# mainboard_motor_v1_6.net
KiCad netlist of a schematic drawn in Altium Designer
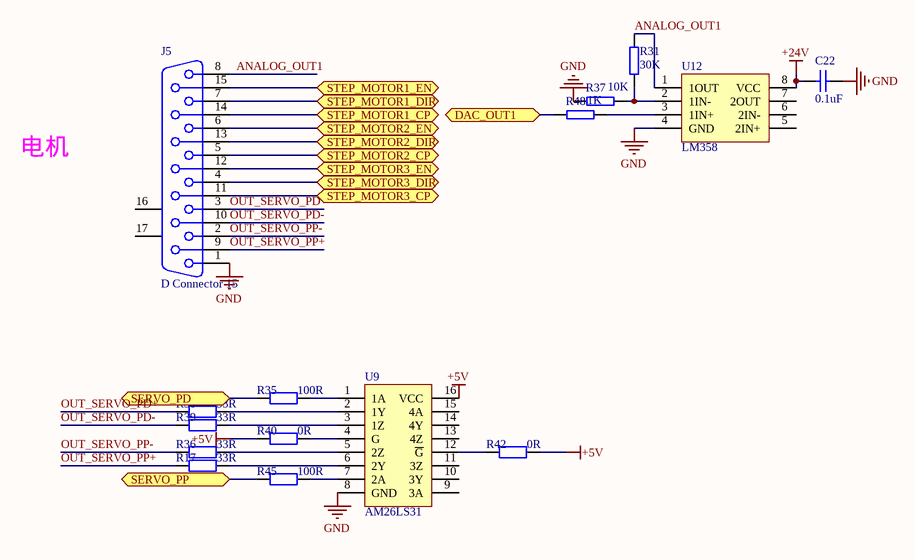
[diagram p0: mainboard_motor.v1.6.SchDoc]

(export (version "E")
  (design (tool "Eeschema 10.0.6"))
  (components
    (comp (ref "C22")
      (value "0.1uF")
      (footprint "0805")
      (description "Capacitor")
      (fields (field (name "PUBLISHER") "Altium Limited"))
      (libsource (lib "TIAN's Schlib") (part "Cap"))
    )
    (comp (ref "J5")
      (value "D Connector 15")
      (footprint "DSUB1.385-2H15")
      (description "Receptacle Assembly, 15 Position, Right Angle")
      (fields (field (name "PUBLISHER") "Altium Limited"))
      (libsource (lib "Miscellaneous Connectors") (part "D Connector 15"))
    )
    (comp (ref "R17")
      (value "33R")
      (footprint "0805")
      (description "Resistor")
      (fields (field (name "PUBLISHER") "Altium Limited"))
      (libsource (lib "TIAN's Schlib") (part "Res2"))
    )
    (comp (ref "R31")
      (value "30K")
      (footprint "0805")
      (description "电阻")
      (libsource (lib "Component") (part "RES"))
    )
    (comp (ref "R35")
      (value "100R")
      (footprint "0805")
      (description "Resistor")
      (fields (field (name "PUBLISHER") "Altium Limited"))
      (libsource (lib "TIAN's Schlib") (part "Res2"))
    )
    (comp (ref "R36")
      (value "33R")
      (footprint "0805")
      (description "Resistor")
      (fields (field (name "PUBLISHER") "Altium Limited"))
      (libsource (lib "TIAN's Schlib") (part "Res2"))
    )
    (comp (ref "R37")
      (value "10K")
      (footprint "0805")
      (description "电阻")
      (libsource (lib "Component") (part "RES"))
    )
    (comp (ref "R38")
      (value "33R")
      (footprint "0805")
      (description "Resistor")
      (fields (field (name "PUBLISHER") "Altium Limited"))
      (libsource (lib "TIAN's Schlib") (part "Res2"))
    )
    (comp (ref "R39")
      (value "33R")
      (footprint "0805")
      (description "Resistor")
      (fields (field (name "PUBLISHER") "Altium Limited"))
      (libsource (lib "TIAN's Schlib") (part "Res2"))
    )
    (comp (ref "R40")
      (value "0R")
      (footprint "0805")
      (description "Resistor")
      (fields (field (name "PUBLISHER") "Altium Limited"))
      (libsource (lib "TIAN's Schlib") (part "Res2"))
    )
    (comp (ref "R42")
      (value "0R")
      (footprint "0805")
      (description "Resistor")
      (fields (field (name "PUBLISHER") "Altium Limited"))
      (libsource (lib "TIAN's Schlib") (part "Res2"))
    )
    (comp (ref "R45")
      (value "100R")
      (footprint "0805")
      (description "Resistor")
      (fields (field (name "PUBLISHER") "Altium Limited"))
      (libsource (lib "TIAN's Schlib") (part "Res2"))
    )
    (comp (ref "R48")
      (value "1K")
      (footprint "0805")
      (description "电阻")
      (libsource (lib "Component") (part "RES"))
    )
    (comp (ref "U9") (value "AM26LS31") (footprint "SO-16") (libsource (lib "Chip") (part "AM26LS31")))
    (comp (ref "U12") (value "LM358") (footprint "SO-8") (libsource (lib "Chip") (part "LM358")))
  )
  (nets
    (net (code "1") (name "+5V") (class "Default")
      (node (ref "R40") (pin "2") (pinfunction "2_2") (pintype "passive"))
      (node (ref "R42") (pin "1") (pinfunction "1_1") (pintype "passive"))
      (node (ref "U9") (pin "16") (pinfunction "VCC_16") (pintype "passive"))
    )
    (net (code "2") (name "+24V") (class "Default")
      (node (ref "C22") (pin "2") (pinfunction "2_2") (pintype "passive"))
      (node (ref "U12") (pin "8") (pinfunction "VCC_8") (pintype "passive"))
    )
    (net (code "3") (name "/ANALOG_OUT1") (class "Default")
      (node (ref "J5") (pin "8") (pinfunction "8_8") (pintype "passive"))
      (node (ref "R31") (pin "1") (pinfunction "1_1") (pintype "passive"))
      (node (ref "U12") (pin "1") (pinfunction "1OUT_1") (pintype "passive"))
    )
    (net (code "4") (name "/DAC_OUT1") (class "Default")
      (node (ref "R48") (pin "2") (pinfunction "2_2") (pintype "passive"))
    )
    (net (code "5") (name "/OUT_SERVO_PD+") (class "Default")
      (node (ref "J5") (pin "3") (pinfunction "3_3") (pintype "passive"))
      (node (ref "R38") (pin "2") (pinfunction "2_2") (pintype "passive"))
    )
    (net (code "6") (name "/OUT_SERVO_PD-") (class "Default")
      (node (ref "J5") (pin "10") (pinfunction "10_10") (pintype "passive"))
      (node (ref "R39") (pin "2") (pinfunction "2_2") (pintype "passive"))
    )
    (net (code "7") (name "/OUT_SERVO_PP+") (class "Default")
      (node (ref "J5") (pin "9") (pinfunction "9_9") (pintype "passive"))
      (node (ref "R17") (pin "2") (pinfunction "2_2") (pintype "passive"))
    )
    (net (code "8") (name "/OUT_SERVO_PP-") (class "Default")
      (node (ref "J5") (pin "2") (pinfunction "2_2") (pintype "passive"))
      (node (ref "R36") (pin "2") (pinfunction "2_2") (pintype "passive"))
    )
    (net (code "9") (name "/SERVO_PD") (class "Default")
      (node (ref "R35") (pin "2") (pinfunction "2_2") (pintype "passive"))
    )
    (net (code "10") (name "/SERVO_PP") (class "Default")
      (node (ref "R45") (pin "2") (pinfunction "2_2") (pintype "passive"))
    )
    (net (code "11") (name "/STEP_MOTOR1_CP") (class "Default")
      (node (ref "J5") (pin "14") (pinfunction "14_14") (pintype "passive"))
    )
    (net (code "12") (name "/STEP_MOTOR1_DIR") (class "Default")
      (node (ref "J5") (pin "7") (pinfunction "7_7") (pintype "passive"))
    )
    (net (code "13") (name "/STEP_MOTOR1_EN") (class "Default")
      (node (ref "J5") (pin "15") (pinfunction "15_15") (pintype "passive"))
    )
    (net (code "14") (name "/STEP_MOTOR2_CP") (class "Default")
      (node (ref "J5") (pin "5") (pinfunction "5_5") (pintype "passive"))
    )
    (net (code "15") (name "/STEP_MOTOR2_DIR") (class "Default")
      (node (ref "J5") (pin "13") (pinfunction "13_13") (pintype "passive"))
    )
    (net (code "16") (name "/STEP_MOTOR2_EN") (class "Default")
      (node (ref "J5") (pin "6") (pinfunction "6_6") (pintype "passive"))
    )
    (net (code "17") (name "/STEP_MOTOR3_CP") (class "Default")
      (node (ref "J5") (pin "11") (pinfunction "11_11") (pintype "passive"))
    )
    (net (code "18") (name "/STEP_MOTOR3_DIR") (class "Default")
      (node (ref "J5") (pin "4") (pinfunction "4_4") (pintype "passive"))
    )
    (net (code "19") (name "/STEP_MOTOR3_EN") (class "Default")
      (node (ref "J5") (pin "12") (pinfunction "12_12") (pintype "passive"))
    )
    (net (code "20") (name "GND") (class "Default")
      (node (ref "C22") (pin "1") (pinfunction "1_1") (pintype "passive"))
      (node (ref "J5") (pin "1") (pinfunction "1_1") (pintype "passive"))
      (node (ref "R37") (pin "2") (pinfunction "2_2") (pintype "passive"))
      (node (ref "U12") (pin "4") (pinfunction "GND_4") (pintype "passive"))
      (node (ref "U9") (pin "8") (pinfunction "GND_8") (pintype "passive"))
    )
    (net (code "21") (name "Net-(U9-1A)") (class "Default")
      (node (ref "R35") (pin "1") (pinfunction "1_1") (pintype "passive"))
      (node (ref "U9") (pin "1") (pinfunction "1A_1") (pintype "passive"))
    )
    (net (code "22") (name "Net-(U9-1Y)") (class "Default")
      (node (ref "R38") (pin "1") (pinfunction "1_1") (pintype "passive"))
      (node (ref "U9") (pin "2") (pinfunction "1Y_2") (pintype "passive"))
    )
    (net (code "23") (name "Net-(U9-1Z)") (class "Default")
      (node (ref "R39") (pin "1") (pinfunction "1_1") (pintype "passive"))
      (node (ref "U9") (pin "3") (pinfunction "1Z_3") (pintype "passive"))
    )
    (net (code "24") (name "Net-(U9-2A)") (class "Default")
      (node (ref "R45") (pin "1") (pinfunction "1_1") (pintype "passive"))
      (node (ref "U9") (pin "7") (pinfunction "2A_7") (pintype "passive"))
    )
    (net (code "25") (name "Net-(U9-2Y)") (class "Default")
      (node (ref "R17") (pin "1") (pinfunction "1_1") (pintype "passive"))
      (node (ref "U9") (pin "6") (pinfunction "2Y_6") (pintype "passive"))
    )
    (net (code "26") (name "Net-(U9-2Z)") (class "Default")
      (node (ref "R36") (pin "1") (pinfunction "1_1") (pintype "passive"))
      (node (ref "U9") (pin "5") (pinfunction "2Z_5") (pintype "passive"))
    )
    (net (code "27") (name "Net-(U9-G)") (class "Default")
      (node (ref "R40") (pin "1") (pinfunction "1_1") (pintype "passive"))
      (node (ref "U9") (pin "4") (pinfunction "G_4") (pintype "passive"))
    )
    (net (code "28") (name "Net-(U9-~{G})") (class "Default")
      (node (ref "R42") (pin "2") (pinfunction "2_2") (pintype "passive"))
      (node (ref "U9") (pin "12") (pinfunction "~{G}_12") (pintype "passive"))
    )
    (net (code "29") (name "Net-(U12-1IN+)") (class "Default")
      (node (ref "R48") (pin "1") (pinfunction "1_1") (pintype "passive"))
      (node (ref "U12") (pin "3") (pinfunction "1IN+_3") (pintype "passive"))
    )
    (net (code "30") (name "Net-(U12-1IN-)") (class "Default")
      (node (ref "R31") (pin "2") (pinfunction "2_2") (pintype "passive"))
      (node (ref "R37") (pin "1") (pinfunction "1_1") (pintype "passive"))
      (node (ref "U12") (pin "2") (pinfunction "1IN-_2") (pintype "passive"))
    )
    (net (code "31") (name "unconnected-(J5-MH1-Pad16)") (class "Default")
      (node (ref "J5") (pin "16") (pinfunction "MH1_16") (pintype "passive"))
    )
    (net (code "32") (name "unconnected-(J5-MH2-Pad17)") (class "Default")
      (node (ref "J5") (pin "17") (pinfunction "MH2_17") (pintype "passive"))
    )
    (net (code "33") (name "unconnected-(U9-3A-Pad9)") (class "Default")
      (node (ref "U9") (pin "9") (pinfunction "3A_9") (pintype "passive"))
    )
    (net (code "34") (name "unconnected-(U9-3Y-Pad10)") (class "Default")
      (node (ref "U9") (pin "10") (pinfunction "3Y_10") (pintype "passive"))
    )
    (net (code "35") (name "unconnected-(U9-3Z-Pad11)") (class "Default")
      (node (ref "U9") (pin "11") (pinfunction "3Z_11") (pintype "passive"))
    )
    (net (code "36") (name "unconnected-(U9-4A-Pad15)") (class "Default")
      (node (ref "U9") (pin "15") (pinfunction "4A_15") (pintype "passive"))
    )
    (net (code "37") (name "unconnected-(U9-4Y-Pad14)") (class "Default")
      (node (ref "U9") (pin "14") (pinfunction "4Y_14") (pintype "passive"))
    )
    (net (code "38") (name "unconnected-(U9-4Z-Pad13)") (class "Default")
      (node (ref "U9") (pin "13") (pinfunction "4Z_13") (pintype "passive"))
    )
    (net (code "39") (name "unconnected-(U12-2IN+-Pad5)") (class "Default")
      (node (ref "U12") (pin "5") (pinfunction "2IN+_5") (pintype "passive"))
    )
    (net (code "40") (name "unconnected-(U12-2IN--Pad6)") (class "Default")
      (node (ref "U12") (pin "6") (pinfunction "2IN-_6") (pintype "passive"))
    )
    (net (code "41") (name "unconnected-(U12-2OUT-Pad7)") (class "Default")
      (node (ref "U12") (pin "7") (pinfunction "2OUT_7") (pintype "passive"))
    )
  )
)
